# psu.net
KiCad netlist of a schematic drawn in EAGLE
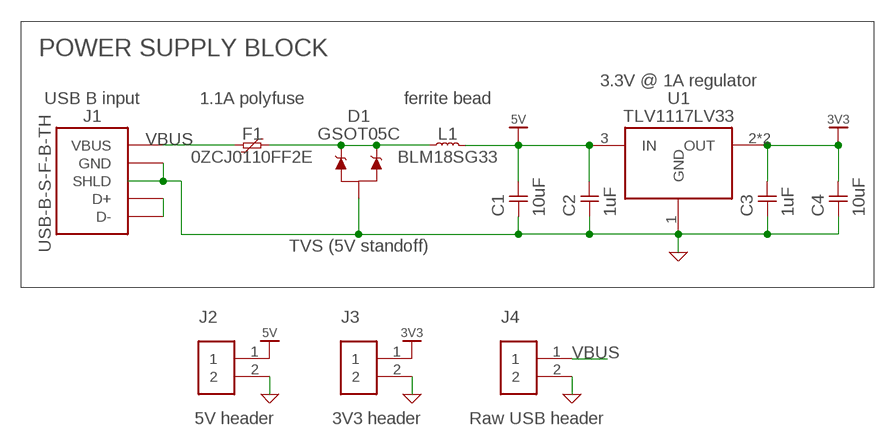
[diagram p0: schematic, sheet 1]

(export (version "E")
  (design (tool "Eeschema 10.0.6"))
  (components
    (comp (ref "C1")
      (value "10uF")
      (footprint "eagle-import:0805")
      (libsource (lib "eagle-import") (part "C0805"))
    )
    (comp (ref "C2")
      (value "1uF")
      (footprint "eagle-import:0603")
      (libsource (lib "eagle-import") (part "C0603"))
    )
    (comp (ref "C3")
      (value "1uF")
      (footprint "eagle-import:0603")
      (libsource (lib "eagle-import") (part "C0603"))
    )
    (comp (ref "C4")
      (value "10uF")
      (footprint "eagle-import:0805")
      (libsource (lib "eagle-import") (part "C0805"))
    )
    (comp (ref "D1")
      (value "GSOT05C")
      (footprint "eagle-import:SOT23-3")
      (libsource (lib "eagle-import") (part "GSOT05C"))
    )
    (comp (ref "F1")
      (value "0ZCJ0110FF2E")
      (footprint "eagle-import:1206")
      (libsource (lib "eagle-import") (part "POLYFUSE-1206"))
    )
    (comp (ref "J1")
      (value "USB-B-S-F-B-TH")
      (footprint "eagle-import:USB-B-SAMTEC")
      (libsource (lib "eagle-import") (part "USB-B-SAMTEC"))
    )
    (comp (ref "J2")
      (value "HEADER_100MIL_1ROW_2")
      (footprint "eagle-import:HEADER_100MIL_1ROW_2")
      (libsource (lib "eagle-import") (part "HEADER_100MIL_1ROW_2"))
    )
    (comp (ref "J3")
      (value "HEADER_100MIL_1ROW_2")
      (footprint "eagle-import:HEADER_100MIL_1ROW_2")
      (libsource (lib "eagle-import") (part "HEADER_100MIL_1ROW_2"))
    )
    (comp (ref "J4")
      (value "HEADER_100MIL_1ROW_2")
      (footprint "eagle-import:HEADER_100MIL_1ROW_2")
      (libsource (lib "eagle-import") (part "HEADER_100MIL_1ROW_2"))
    )
    (comp (ref "L1")
      (value "BLM18SG33")
      (footprint "eagle-import:0603")
      (libsource (lib "eagle-import") (part "FERRITE_BEAD-0603"))
    )
    (comp (ref "U1")
      (value "TLV1117LV33")
      (footprint "eagle-import:SOT223-3")
      (libsource (lib "eagle-import") (part "TLV1117LV33DCY"))
    )
  )
  (nets
    (net (code "1") (name "/VBUS") (class "Default")
      (node (ref "F1") (pin "1") (pinfunction "1_1") (pintype "passive"))
      (node (ref "J1") (pin "1") (pinfunction "VBUS_1") (pintype "power_in"))
      (node (ref "J4") (pin "1") (pinfunction "1_1") (pintype "passive"))
    )
    (net (code "2") (name "3V3") (class "Default")
      (node (ref "C3") (pin "1") (pinfunction "2_1") (pintype "passive"))
      (node (ref "C4") (pin "1") (pinfunction "2_1") (pintype "passive"))
      (node (ref "J3") (pin "1") (pinfunction "1_1") (pintype "passive"))
      (node (ref "U1") (pin "2") (pinfunction "OUT_2") (pintype "power_in"))
      (node (ref "U1") (pin "4") (pinfunction "OUT_4") (pintype "power_in"))
    )
    (net (code "3") (name "5V") (class "Default")
      (node (ref "C1") (pin "1") (pinfunction "2_1") (pintype "passive"))
      (node (ref "C2") (pin "1") (pinfunction "2_1") (pintype "passive"))
      (node (ref "J2") (pin "1") (pinfunction "1_1") (pintype "passive"))
      (node (ref "L1") (pin "2") (pinfunction "2_2") (pintype "passive"))
      (node (ref "U1") (pin "3") (pinfunction "IN_3") (pintype "power_in"))
    )
    (net (code "4") (name "DGND") (class "Default")
      (node (ref "C1") (pin "2") (pinfunction "1_2") (pintype "passive"))
      (node (ref "C2") (pin "2") (pinfunction "1_2") (pintype "passive"))
      (node (ref "C3") (pin "2") (pinfunction "1_2") (pintype "passive"))
      (node (ref "C4") (pin "2") (pinfunction "1_2") (pintype "passive"))
      (node (ref "D1") (pin "3") (pinfunction "A_3") (pintype "passive"))
      (node (ref "J1") (pin "4") (pinfunction "GND_4") (pintype "power_in"))
      (node (ref "J1") (pin "5") (pinfunction "SHLD_5") (pintype "power_in"))
      (node (ref "J1") (pin "6") (pinfunction "SHLD_6") (pintype "power_in"))
      (node (ref "J2") (pin "2") (pinfunction "2_2") (pintype "passive"))
      (node (ref "J3") (pin "2") (pinfunction "2_2") (pintype "passive"))
      (node (ref "J4") (pin "2") (pinfunction "2_2") (pintype "passive"))
      (node (ref "U1") (pin "1") (pinfunction "GND_1") (pintype "power_in"))
    )
    (net (code "5") (name "Net-(D1-C1)") (class "Default")
      (node (ref "D1") (pin "1") (pinfunction "C1_1") (pintype "passive"))
      (node (ref "D1") (pin "2") (pinfunction "C2_2") (pintype "passive"))
      (node (ref "F1") (pin "2") (pinfunction "2_2") (pintype "passive"))
      (node (ref "L1") (pin "1") (pinfunction "1_1") (pintype "passive"))
    )
    (net (code "6") (name "Net-(J1-D+)") (class "Default")
      (node (ref "J1") (pin "2") (pinfunction "D-_2") (pintype "bidirectional"))
      (node (ref "J1") (pin "3") (pinfunction "D+_3") (pintype "bidirectional"))
    )
  )
)
